# MAX9857A_audio_amp.net
KiCad netlist of a schematic drawn in Altium Designer
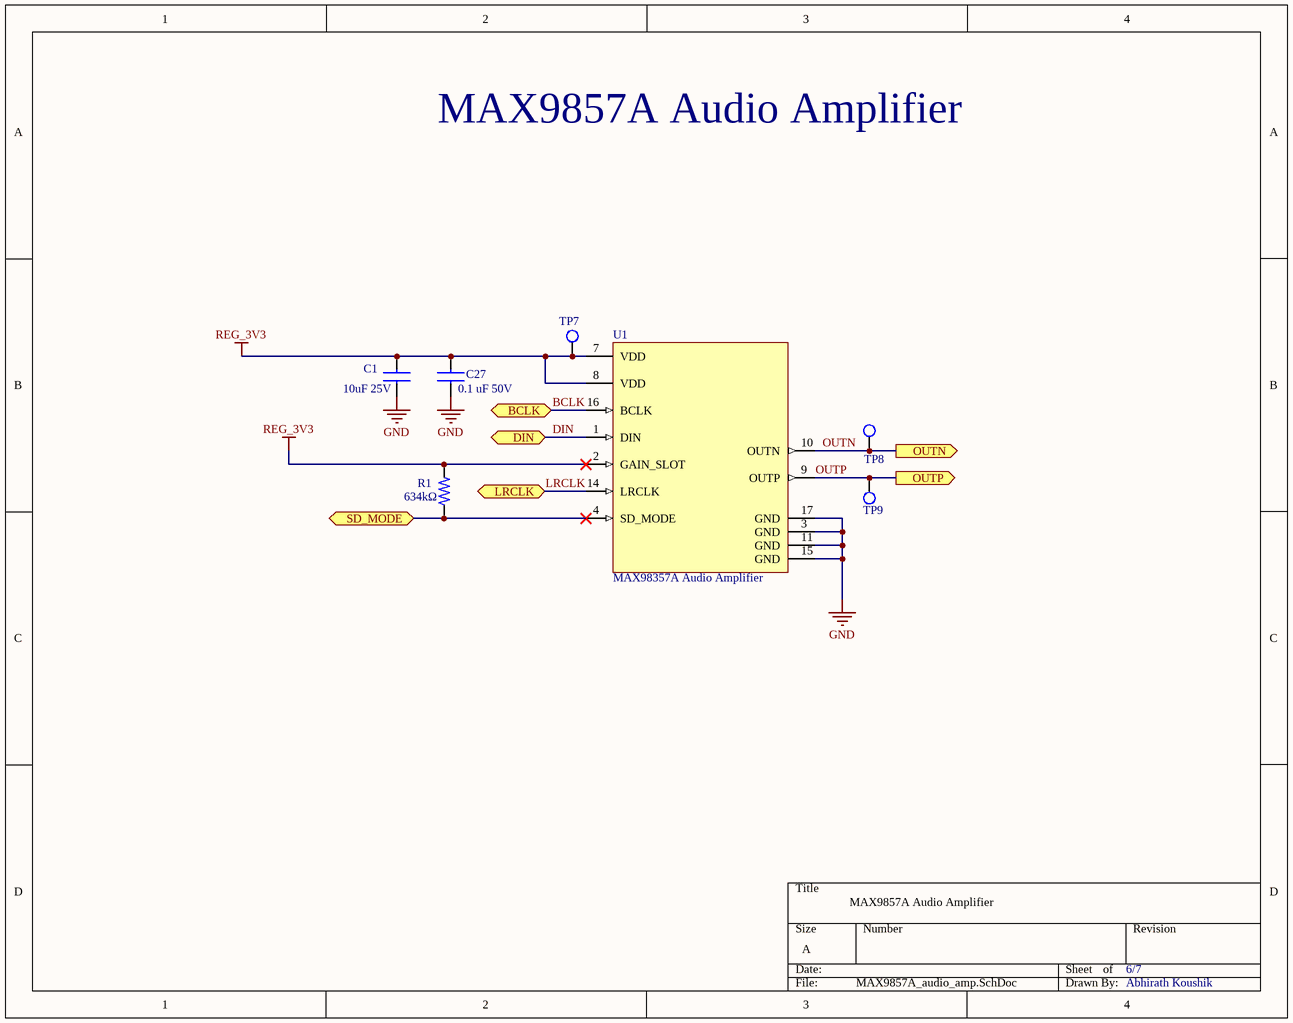
[diagram p0: MAX9857A_audio_amp.SchDoc]

(export (version "E")
  (design (tool "Eeschema 10.0.6"))
  (components
    (comp (ref "C1")
      (value "10uF 25V")
      (footprint "CAP_10")
      (description "Ceramic Capacitor, Ceramic, 25V, 10% +Tol, 10% -Tol, X5R, 15% TC, 10uF, Surface Mount, 0805")
      (fields
        (field (name "MANUFACTURER") "Murata")
        (field (name "MANUFACTURER PART NUMBER") "GRM21BR61E106KA73K")
      )
      (libsource (lib "LPEDT_Pulse_Project_SCH_Library") (part "GRM21BR61E106KA73K"))
    )
    (comp (ref "C27")
      (value "0.1 uF 50V")
      (footprint "CAPC1608X90N")
      (description "0.10uF Tol.1%. Rated voltage 50Vdc 125C SMD capacitor C0G(EIA) with capacitance")
      (fields
        (field (name "MP") "GCM31C5C1H104FA16L")
        (field (name "DIGI-KEY_PART_NUMBER") "490-GCM31C5C1H104FA16LTR-ND")
      )
      (libsource (lib "LPEDT_Pulse_Project_SCH_Library") (part "GCM31C5C1H104FA16L"))
    )
    (comp (ref "R1")
      (value "634kΩ")
      (footprint "634k 0603")
      (description "Res Thick Film 0603 634K Ohm 1% 0.1W(1/10W) ±100ppm/C Pad SMD Automotive T/R")
      (fields
        (field (name "MANUFACTURER") "Stackpole Electronics")
        (field (name "MANUFACTURER PART NUMBER") "RMCF0603FT634K")
      )
      (libsource (lib "LPEDT_Pulse_Project_SCH_Library") (part "RMCF0603FT634K"))
    )
    (comp (ref "TP7")
      (value "Test Point")
      (footprint "Test Point")
      (libsource (lib "LPEDT_Pulse_Project_SCH_Library") (part "Test Point"))
    )
    (comp (ref "TP8")
      (value "Test Point")
      (footprint "Test Point")
      (libsource (lib "LPEDT_Pulse_Project_SCH_Library") (part "Test Point"))
    )
    (comp (ref "TP9")
      (value "Test Point")
      (footprint "Test Point")
      (libsource (lib "LPEDT_Pulse_Project_SCH_Library") (part "Test Point"))
    )
    (comp (ref "U1")
      (value "MAX98357A Audio Amplifier")
      (footprint "MAX98357_QFN_T1633_4")
      (description "MAX98357A Series 5.5 V 3.2 W PCM Input Class D Audio Power Amplifier - TQFN-16")
      (fields
        (field (name "MANUFACTURER") "Analog Devices")
        (field (name "MANUFACTURER PART NUMBER") "MAX98357AETE+T")
      )
      (libsource (lib "LPEDT_Pulse_Project_SCH_Library") (part "MAX98357AETE+T"))
    )
  )
  (nets
    (net (code "1") (name "/BCLK") (class "Default")
      (node (ref "U1") (pin "16") (pinfunction "BCLK_16") (pintype "input"))
    )
    (net (code "2") (name "/DIN") (class "Default")
      (node (ref "U1") (pin "1") (pinfunction "DIN_1") (pintype "input"))
    )
    (net (code "3") (name "/LRCLK") (class "Default")
      (node (ref "U1") (pin "14") (pinfunction "LRCLK_14") (pintype "input"))
    )
    (net (code "4") (name "/OUTN") (class "Default")
      (node (ref "TP8") (pin "1") (pinfunction "1_1") (pintype "passive"))
      (node (ref "U1") (pin "10") (pinfunction "OUTN_10") (pintype "output"))
    )
    (net (code "5") (name "/OUTP") (class "Default")
      (node (ref "TP9") (pin "1") (pinfunction "1_1") (pintype "passive"))
      (node (ref "U1") (pin "9") (pinfunction "OUTP_9") (pintype "output"))
    )
    (net (code "6") (name "/SD_MODE") (class "Default")
      (node (ref "R1") (pin "1") (pinfunction "1_1") (pintype "passive"))
      (node (ref "U1") (pin "4") (pinfunction "SD_MODE_4") (pintype "input"))
    )
    (net (code "7") (name "GND") (class "Default")
      (node (ref "C1") (pin "1") (pinfunction "1_1") (pintype "passive"))
      (node (ref "C27") (pin "2") (pinfunction "2_2") (pintype "passive"))
      (node (ref "U1") (pin "11") (pinfunction "GND_11") (pintype "power_in"))
      (node (ref "U1") (pin "15") (pinfunction "GND_15") (pintype "power_in"))
      (node (ref "U1") (pin "17") (pinfunction "GND_17") (pintype "power_in"))
      (node (ref "U1") (pin "3") (pinfunction "GND_3") (pintype "power_in"))
    )
    (net (code "8") (name "REG_3V3") (class "Default")
      (node (ref "C1") (pin "2") (pinfunction "2_2") (pintype "passive"))
      (node (ref "C27") (pin "1") (pinfunction "1_1") (pintype "passive"))
      (node (ref "R1") (pin "2") (pinfunction "2_2") (pintype "passive"))
      (node (ref "TP7") (pin "1") (pinfunction "1_1") (pintype "passive"))
      (node (ref "U1") (pin "2") (pinfunction "GAIN_SLOT_2") (pintype "input"))
      (node (ref "U1") (pin "7") (pinfunction "VDD_7") (pintype "power_in"))
      (node (ref "U1") (pin "8") (pinfunction "VDD_8") (pintype "power_in"))
    )
  )
)
